# 00_EEG_AFE.net
KiCad netlist of a schematic drawn in Altium Designer
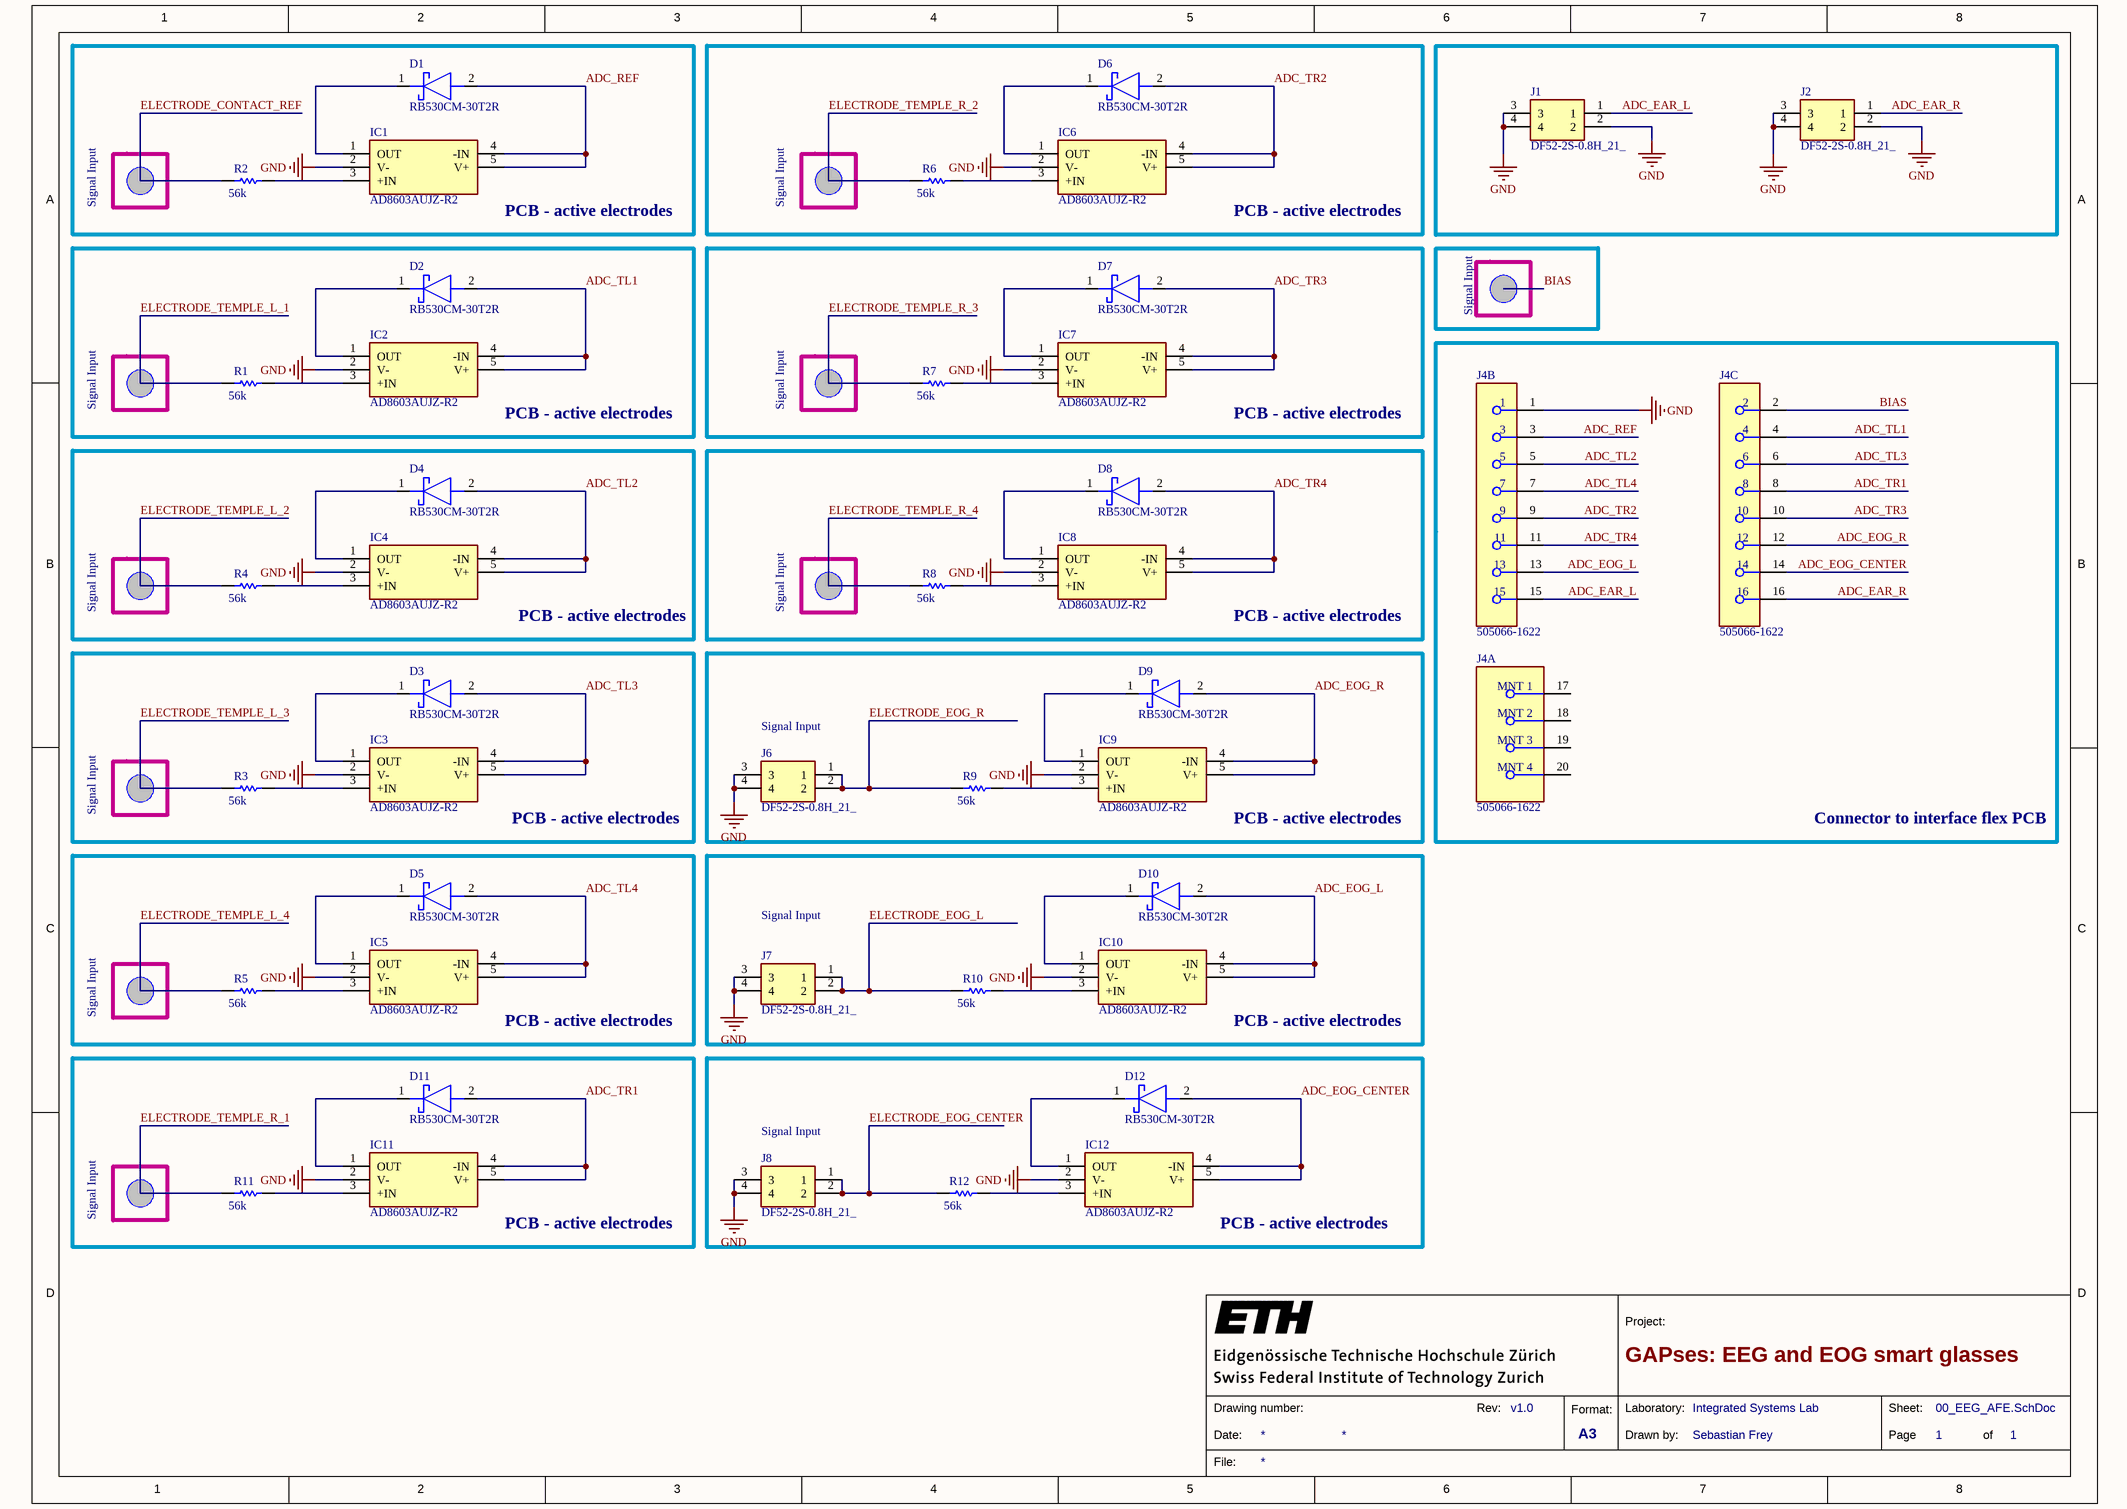
[diagram p0: 00_EEG_AFE.SchDoc]

(export (version "E")
  (design (tool "Eeschema 10.0.6"))
  (components
    (comp (ref "D1")
      (value "RB530CM-30T2R")
      (footprint "SamacSys:RB886CST2RA")
      (description "Schottky Diode")
      (fields (field (name "MOUSER PART NUMBER") "755-RB530CM-30T2R"))
      (libsource (lib "*") (part "RB530CM-30T2R"))
    )
    (comp (ref "D2")
      (value "RB530CM-30T2R")
      (footprint "SamacSys:RB886CST2RA")
      (description "Schottky Diode")
      (fields (field (name "MOUSER PART NUMBER") "755-RB530CM-30T2R"))
      (libsource (lib "*") (part "RB530CM-30T2R"))
    )
    (comp (ref "D3")
      (value "RB530CM-30T2R")
      (footprint "SamacSys:RB886CST2RA")
      (description "Schottky Diode")
      (fields (field (name "MOUSER PART NUMBER") "755-RB530CM-30T2R"))
      (libsource (lib "*") (part "RB530CM-30T2R"))
    )
    (comp (ref "D4")
      (value "RB530CM-30T2R")
      (footprint "SamacSys:RB886CST2RA")
      (description "Schottky Diode")
      (fields (field (name "MOUSER PART NUMBER") "755-RB530CM-30T2R"))
      (libsource (lib "*") (part "RB530CM-30T2R"))
    )
    (comp (ref "D5")
      (value "RB530CM-30T2R")
      (footprint "SamacSys:RB886CST2RA")
      (description "Schottky Diode")
      (fields (field (name "MOUSER PART NUMBER") "755-RB530CM-30T2R"))
      (libsource (lib "*") (part "RB530CM-30T2R"))
    )
    (comp (ref "D6")
      (value "RB530CM-30T2R")
      (footprint "SamacSys:RB886CST2RA")
      (description "Schottky Diode")
      (fields (field (name "MOUSER PART NUMBER") "755-RB530CM-30T2R"))
      (libsource (lib "*") (part "RB530CM-30T2R"))
    )
    (comp (ref "D7")
      (value "RB530CM-30T2R")
      (footprint "SamacSys:RB886CST2RA")
      (description "Schottky Diode")
      (fields (field (name "MOUSER PART NUMBER") "755-RB530CM-30T2R"))
      (libsource (lib "*") (part "RB530CM-30T2R"))
    )
    (comp (ref "D8")
      (value "RB530CM-30T2R")
      (footprint "SamacSys:RB886CST2RA")
      (description "Schottky Diode")
      (fields (field (name "MOUSER PART NUMBER") "755-RB530CM-30T2R"))
      (libsource (lib "*") (part "RB530CM-30T2R"))
    )
    (comp (ref "D9")
      (value "RB530CM-30T2R")
      (footprint "SamacSys:RB886CST2RA")
      (description "Schottky Diode")
      (fields (field (name "MOUSER PART NUMBER") "755-RB530CM-30T2R"))
      (libsource (lib "*") (part "RB530CM-30T2R"))
    )
    (comp (ref "D10")
      (value "RB530CM-30T2R")
      (footprint "SamacSys:RB886CST2RA")
      (description "Schottky Diode")
      (fields (field (name "MOUSER PART NUMBER") "755-RB530CM-30T2R"))
      (libsource (lib "*") (part "RB530CM-30T2R"))
    )
    (comp (ref "D11")
      (value "RB530CM-30T2R")
      (footprint "SamacSys:RB886CST2RA")
      (description "Schottky Diode")
      (fields (field (name "MOUSER PART NUMBER") "755-RB530CM-30T2R"))
      (libsource (lib "*") (part "RB530CM-30T2R"))
    )
    (comp (ref "D12")
      (value "RB530CM-30T2R")
      (footprint "SamacSys:RB886CST2RA")
      (description "Schottky Diode")
      (fields (field (name "MOUSER PART NUMBER") "755-RB530CM-30T2R"))
      (libsource (lib "*") (part "RB530CM-30T2R"))
    )
    (comp (ref "IC1")
      (value "AD8603AUJZ-R2")
      (footprint "EEG_PcbLib:SOT95P280X100-5N")
      (description "Integrated Circuit")
      (libsource (lib "EEG_SchLib") (part "AD8603AUJZ-R2"))
    )
    (comp (ref "IC2")
      (value "AD8603AUJZ-R2")
      (footprint "EEG_PcbLib:SOT95P280X100-5N")
      (description "Integrated Circuit")
      (libsource (lib "EEG_SchLib") (part "AD8603AUJZ-R2"))
    )
    (comp (ref "IC3")
      (value "AD8603AUJZ-R2")
      (footprint "EEG_PcbLib:SOT95P280X100-5N")
      (description "Integrated Circuit")
      (libsource (lib "EEG_SchLib") (part "AD8603AUJZ-R2"))
    )
    (comp (ref "IC4")
      (value "AD8603AUJZ-R2")
      (footprint "EEG_PcbLib:SOT95P280X100-5N")
      (description "Integrated Circuit")
      (libsource (lib "EEG_SchLib") (part "AD8603AUJZ-R2"))
    )
    (comp (ref "IC5")
      (value "AD8603AUJZ-R2")
      (footprint "EEG_PcbLib:SOT95P280X100-5N")
      (description "Integrated Circuit")
      (libsource (lib "EEG_SchLib") (part "AD8603AUJZ-R2"))
    )
    (comp (ref "IC6")
      (value "AD8603AUJZ-R2")
      (footprint "EEG_PcbLib:SOT95P280X100-5N")
      (description "Integrated Circuit")
      (libsource (lib "EEG_SchLib") (part "AD8603AUJZ-R2"))
    )
    (comp (ref "IC7")
      (value "AD8603AUJZ-R2")
      (footprint "EEG_PcbLib:SOT95P280X100-5N")
      (description "Integrated Circuit")
      (libsource (lib "EEG_SchLib") (part "AD8603AUJZ-R2"))
    )
    (comp (ref "IC8")
      (value "AD8603AUJZ-R2")
      (footprint "EEG_PcbLib:SOT95P280X100-5N")
      (description "Integrated Circuit")
      (libsource (lib "EEG_SchLib") (part "AD8603AUJZ-R2"))
    )
    (comp (ref "IC9")
      (value "AD8603AUJZ-R2")
      (footprint "EEG_PcbLib:SOT95P280X100-5N")
      (description "Integrated Circuit")
      (libsource (lib "EEG_SchLib") (part "AD8603AUJZ-R2"))
    )
    (comp (ref "IC10")
      (value "AD8603AUJZ-R2")
      (footprint "EEG_PcbLib:SOT95P280X100-5N")
      (description "Integrated Circuit")
      (libsource (lib "EEG_SchLib") (part "AD8603AUJZ-R2"))
    )
    (comp (ref "IC11")
      (value "AD8603AUJZ-R2")
      (footprint "EEG_PcbLib:SOT95P280X100-5N")
      (description "Integrated Circuit")
      (libsource (lib "EEG_SchLib") (part "AD8603AUJZ-R2"))
    )
    (comp (ref "IC12")
      (value "AD8603AUJZ-R2")
      (footprint "EEG_PcbLib:SOT95P280X100-5N")
      (description "Integrated Circuit")
      (libsource (lib "EEG_SchLib") (part "AD8603AUJZ-R2"))
    )
    (comp (ref "J1")
      (value "DF52-2S-0.8H_21_")
      (footprint "SamacSys:DF522S08H21")
      (description "Connector")
      (fields
        (field (name "MANUFACTURER_PART_NUMBER") "DF52-2S-0.8H(21)")
        (field (name "MOUSER PART NUMBER") "798-DF52-2S-0.8H21")
      )
      (libsource (lib "SamacSys") (part "DF52-2S-0.8H_21_"))
    )
    (comp (ref "J2")
      (value "DF52-2S-0.8H_21_")
      (footprint "SamacSys:DF522S08H21")
      (description "Connector")
      (fields
        (field (name "MANUFACTURER_PART_NUMBER") "DF52-2S-0.8H(21)")
        (field (name "MOUSER PART NUMBER") "798-DF52-2S-0.8H21")
      )
      (libsource (lib "SamacSys") (part "DF52-2S-0.8H_21_"))
    )
    (comp (ref "J4")
      (value "505066-1622")
      (footprint "FP-505066-1622-MFG")
      (description "CONN RCPT 16POS SMD GOLD")
      (libsource (lib "Altium Content Vault") (part "9cd4949b7c36534f8c09468ececd60b"))
    )
    (comp (ref "J6")
      (value "DF52-2S-0.8H_21_")
      (footprint "SamacSys:DF522S08H21")
      (description "Connector")
      (fields
        (field (name "MANUFACTURER_PART_NUMBER") "DF52-2S-0.8H(21)")
        (field (name "MOUSER PART NUMBER") "798-DF52-2S-0.8H21")
      )
      (libsource (lib "SamacSys") (part "DF52-2S-0.8H_21_"))
    )
    (comp (ref "J7")
      (value "DF52-2S-0.8H_21_")
      (footprint "SamacSys:DF522S08H21")
      (description "Connector")
      (fields
        (field (name "MANUFACTURER_PART_NUMBER") "DF52-2S-0.8H(21)")
        (field (name "MOUSER PART NUMBER") "798-DF52-2S-0.8H21")
      )
      (libsource (lib "SamacSys") (part "DF52-2S-0.8H_21_"))
    )
    (comp (ref "J8")
      (value "DF52-2S-0.8H_21_")
      (footprint "SamacSys:DF522S08H21")
      (description "Connector")
      (fields
        (field (name "MANUFACTURER_PART_NUMBER") "DF52-2S-0.8H(21)")
        (field (name "MOUSER PART NUMBER") "798-DF52-2S-0.8H21")
      )
      (libsource (lib "SamacSys") (part "DF52-2S-0.8H_21_"))
    )
    (comp (ref "R1")
      (value "RC0402JR-0756KL")
      (footprint "RESC1005X40X25LL05T10")
      (fields (field (name "MANUFACTURER") "Yageo / Phycomp") (field (name "RESISTANCE") "56k"))
      (libsource (lib "Altium Content Vault") (part "RES"))
    )
    (comp (ref "R2")
      (value "RC0402JR-0756KL")
      (footprint "RESC1005X40X25LL05T10")
      (fields (field (name "MANUFACTURER") "Yageo / Phycomp") (field (name "RESISTANCE") "56k"))
      (libsource (lib "Altium Content Vault") (part "RES"))
    )
    (comp (ref "R3")
      (value "RC0402JR-0756KL")
      (footprint "RESC1005X40X25LL05T10")
      (fields (field (name "MANUFACTURER") "Yageo / Phycomp") (field (name "RESISTANCE") "56k"))
      (libsource (lib "Altium Content Vault") (part "RES"))
    )
    (comp (ref "R4")
      (value "RC0402JR-0756KL")
      (footprint "RESC1005X40X25LL05T10")
      (fields (field (name "MANUFACTURER") "Yageo / Phycomp") (field (name "RESISTANCE") "56k"))
      (libsource (lib "Altium Content Vault") (part "RES"))
    )
    (comp (ref "R5")
      (value "RC0402JR-0756KL")
      (footprint "RESC1005X40X25LL05T10")
      (fields (field (name "MANUFACTURER") "Yageo / Phycomp") (field (name "RESISTANCE") "56k"))
      (libsource (lib "Altium Content Vault") (part "RES"))
    )
    (comp (ref "R6")
      (value "RC0402JR-0756KL")
      (footprint "RESC1005X40X25LL05T10")
      (fields (field (name "MANUFACTURER") "Yageo / Phycomp") (field (name "RESISTANCE") "56k"))
      (libsource (lib "Altium Content Vault") (part "RES"))
    )
    (comp (ref "R7")
      (value "RC0402JR-0756KL")
      (footprint "RESC1005X40X25LL05T10")
      (fields (field (name "MANUFACTURER") "Yageo / Phycomp") (field (name "RESISTANCE") "56k"))
      (libsource (lib "Altium Content Vault") (part "RES"))
    )
    (comp (ref "R8")
      (value "RC0402JR-0756KL")
      (footprint "RESC1005X40X25LL05T10")
      (fields (field (name "MANUFACTURER") "Yageo / Phycomp") (field (name "RESISTANCE") "56k"))
      (libsource (lib "Altium Content Vault") (part "RES"))
    )
    (comp (ref "R9")
      (value "RC0402JR-0756KL")
      (footprint "RESC1005X40X25LL05T10")
      (fields (field (name "MANUFACTURER") "Yageo / Phycomp") (field (name "RESISTANCE") "56k"))
      (libsource (lib "Altium Content Vault") (part "RES"))
    )
    (comp (ref "R10")
      (value "RC0402JR-0756KL")
      (footprint "RESC1005X40X25LL05T10")
      (fields (field (name "MANUFACTURER") "Yageo / Phycomp") (field (name "RESISTANCE") "56k"))
      (libsource (lib "Altium Content Vault") (part "RES"))
    )
    (comp (ref "R11")
      (value "RC0402JR-0756KL")
      (footprint "RESC1005X40X25LL05T10")
      (fields (field (name "MANUFACTURER") "Yageo / Phycomp") (field (name "RESISTANCE") "56k"))
      (libsource (lib "Altium Content Vault") (part "RES"))
    )
    (comp (ref "R12")
      (value "RC0402JR-0756KL")
      (footprint "RESC1005X40X25LL05T10")
      (fields (field (name "MANUFACTURER") "Yageo / Phycomp") (field (name "RESISTANCE") "56k"))
      (libsource (lib "Altium Content Vault") (part "RES"))
    )
  )
  (nets
    (net (code "1") (name "/ADC_EAR_L") (class "Default")
      (node (ref "J1") (pin "1") (pinfunction "1_1") (pintype "passive"))
      (node (ref "J4") (pin "15") (pinfunction "15_15") (pintype "passive"))
    )
    (net (code "2") (name "/ADC_EAR_R") (class "Default")
      (node (ref "J2") (pin "1") (pinfunction "1_1") (pintype "passive"))
      (node (ref "J4") (pin "16") (pinfunction "16_16") (pintype "passive"))
    )
    (net (code "3") (name "/ADC_EOG_CENTER") (class "Default")
      (node (ref "D12") (pin "2") (pinfunction "A_2") (pintype "passive"))
      (node (ref "IC12") (pin "4") (pinfunction "-IN_4") (pintype "passive"))
      (node (ref "IC12") (pin "5") (pinfunction "V+_5") (pintype "passive"))
      (node (ref "J4") (pin "14") (pinfunction "14_14") (pintype "passive"))
    )
    (net (code "4") (name "/ADC_EOG_L") (class "Default")
      (node (ref "D10") (pin "2") (pinfunction "A_2") (pintype "passive"))
      (node (ref "IC10") (pin "4") (pinfunction "-IN_4") (pintype "passive"))
      (node (ref "IC10") (pin "5") (pinfunction "V+_5") (pintype "passive"))
      (node (ref "J4") (pin "13") (pinfunction "13_13") (pintype "passive"))
    )
    (net (code "5") (name "/ADC_EOG_R") (class "Default")
      (node (ref "D9") (pin "2") (pinfunction "A_2") (pintype "passive"))
      (node (ref "IC9") (pin "4") (pinfunction "-IN_4") (pintype "passive"))
      (node (ref "IC9") (pin "5") (pinfunction "V+_5") (pintype "passive"))
      (node (ref "J4") (pin "12") (pinfunction "12_12") (pintype "passive"))
    )
    (net (code "6") (name "/ADC_REF") (class "Default")
      (node (ref "D1") (pin "2") (pinfunction "A_2") (pintype "passive"))
      (node (ref "IC1") (pin "4") (pinfunction "-IN_4") (pintype "passive"))
      (node (ref "IC1") (pin "5") (pinfunction "V+_5") (pintype "passive"))
      (node (ref "J4") (pin "3") (pinfunction "3_3") (pintype "passive"))
    )
    (net (code "7") (name "/ADC_TL1") (class "Default")
      (node (ref "D2") (pin "2") (pinfunction "A_2") (pintype "passive"))
      (node (ref "IC2") (pin "4") (pinfunction "-IN_4") (pintype "passive"))
      (node (ref "IC2") (pin "5") (pinfunction "V+_5") (pintype "passive"))
      (node (ref "J4") (pin "4") (pinfunction "4_4") (pintype "passive"))
    )
    (net (code "8") (name "/ADC_TL2") (class "Default")
      (node (ref "D4") (pin "2") (pinfunction "A_2") (pintype "passive"))
      (node (ref "IC4") (pin "4") (pinfunction "-IN_4") (pintype "passive"))
      (node (ref "IC4") (pin "5") (pinfunction "V+_5") (pintype "passive"))
      (node (ref "J4") (pin "5") (pinfunction "5_5") (pintype "passive"))
    )
    (net (code "9") (name "/ADC_TL3") (class "Default")
      (node (ref "D3") (pin "2") (pinfunction "A_2") (pintype "passive"))
      (node (ref "IC3") (pin "4") (pinfunction "-IN_4") (pintype "passive"))
      (node (ref "IC3") (pin "5") (pinfunction "V+_5") (pintype "passive"))
      (node (ref "J4") (pin "6") (pinfunction "6_6") (pintype "passive"))
    )
    (net (code "10") (name "/ADC_TL4") (class "Default")
      (node (ref "D5") (pin "2") (pinfunction "A_2") (pintype "passive"))
      (node (ref "IC5") (pin "4") (pinfunction "-IN_4") (pintype "passive"))
      (node (ref "IC5") (pin "5") (pinfunction "V+_5") (pintype "passive"))
      (node (ref "J4") (pin "7") (pinfunction "7_7") (pintype "passive"))
    )
    (net (code "11") (name "/ADC_TR1") (class "Default")
      (node (ref "D11") (pin "2") (pinfunction "A_2") (pintype "passive"))
      (node (ref "IC11") (pin "4") (pinfunction "-IN_4") (pintype "passive"))
      (node (ref "IC11") (pin "5") (pinfunction "V+_5") (pintype "passive"))
      (node (ref "J4") (pin "8") (pinfunction "8_8") (pintype "passive"))
    )
    (net (code "12") (name "/ADC_TR2") (class "Default")
      (node (ref "D6") (pin "2") (pinfunction "A_2") (pintype "passive"))
      (node (ref "IC6") (pin "4") (pinfunction "-IN_4") (pintype "passive"))
      (node (ref "IC6") (pin "5") (pinfunction "V+_5") (pintype "passive"))
      (node (ref "J4") (pin "9") (pinfunction "9_9") (pintype "passive"))
    )
    (net (code "13") (name "/ADC_TR3") (class "Default")
      (node (ref "D7") (pin "2") (pinfunction "A_2") (pintype "passive"))
      (node (ref "IC7") (pin "4") (pinfunction "-IN_4") (pintype "passive"))
      (node (ref "IC7") (pin "5") (pinfunction "V+_5") (pintype "passive"))
      (node (ref "J4") (pin "10") (pinfunction "10_10") (pintype "passive"))
    )
    (net (code "14") (name "/ADC_TR4") (class "Default")
      (node (ref "D8") (pin "2") (pinfunction "A_2") (pintype "passive"))
      (node (ref "IC8") (pin "4") (pinfunction "-IN_4") (pintype "passive"))
      (node (ref "IC8") (pin "5") (pinfunction "V+_5") (pintype "passive"))
      (node (ref "J4") (pin "11") (pinfunction "11_11") (pintype "passive"))
    )
    (net (code "15") (name "/BIAS") (class "Default")
      (node (ref "J4") (pin "2") (pinfunction "2_2") (pintype "passive"))
    )
    (net (code "16") (name "/ELECTRODE_CONTACT_REF") (class "Default")
      (node (ref "R2") (pin "1") (pinfunction "1_1") (pintype "passive"))
    )
    (net (code "17") (name "/ELECTRODE_EOG_CENTER") (class "Default")
      (node (ref "J8") (pin "1") (pinfunction "1_1") (pintype "passive"))
      (node (ref "J8") (pin "2") (pinfunction "2_2") (pintype "passive"))
      (node (ref "R12") (pin "1") (pinfunction "1_1") (pintype "passive"))
    )
    (net (code "18") (name "/ELECTRODE_EOG_L") (class "Default")
      (node (ref "J7") (pin "1") (pinfunction "1_1") (pintype "passive"))
      (node (ref "J7") (pin "2") (pinfunction "2_2") (pintype "passive"))
      (node (ref "R10") (pin "1") (pinfunction "1_1") (pintype "passive"))
    )
    (net (code "19") (name "/ELECTRODE_EOG_R") (class "Default")
      (node (ref "J6") (pin "1") (pinfunction "1_1") (pintype "passive"))
      (node (ref "J6") (pin "2") (pinfunction "2_2") (pintype "passive"))
      (node (ref "R9") (pin "1") (pinfunction "1_1") (pintype "passive"))
    )
    (net (code "20") (name "/ELECTRODE_TEMPLE_L_1") (class "Default")
      (node (ref "R1") (pin "1") (pinfunction "1_1") (pintype "passive"))
    )
    (net (code "21") (name "/ELECTRODE_TEMPLE_L_2") (class "Default")
      (node (ref "R4") (pin "1") (pinfunction "1_1") (pintype "passive"))
    )
    (net (code "22") (name "/ELECTRODE_TEMPLE_L_3") (class "Default")
      (node (ref "R3") (pin "1") (pinfunction "1_1") (pintype "passive"))
    )
    (net (code "23") (name "/ELECTRODE_TEMPLE_L_4") (class "Default")
      (node (ref "R5") (pin "1") (pinfunction "1_1") (pintype "passive"))
    )
    (net (code "24") (name "/ELECTRODE_TEMPLE_R_1") (class "Default")
      (node (ref "R11") (pin "1") (pinfunction "1_1") (pintype "passive"))
    )
    (net (code "25") (name "/ELECTRODE_TEMPLE_R_2") (class "Default")
      (node (ref "R6") (pin "1") (pinfunction "1_1") (pintype "passive"))
    )
    (net (code "26") (name "/ELECTRODE_TEMPLE_R_3") (class "Default")
      (node (ref "R7") (pin "1") (pinfunction "1_1") (pintype "passive"))
    )
    (net (code "27") (name "/ELECTRODE_TEMPLE_R_4") (class "Default")
      (node (ref "R8") (pin "1") (pinfunction "1_1") (pintype "passive"))
    )
    (net (code "28") (name "GND") (class "Default")
      (node (ref "IC1") (pin "2") (pinfunction "V-_2") (pintype "passive"))
      (node (ref "IC10") (pin "2") (pinfunction "V-_2") (pintype "passive"))
      (node (ref "IC11") (pin "2") (pinfunction "V-_2") (pintype "passive"))
      (node (ref "IC12") (pin "2") (pinfunction "V-_2") (pintype "passive"))
      (node (ref "IC2") (pin "2") (pinfunction "V-_2") (pintype "passive"))
      (node (ref "IC3") (pin "2") (pinfunction "V-_2") (pintype "passive"))
      (node (ref "IC4") (pin "2") (pinfunction "V-_2") (pintype "passive"))
      (node (ref "IC5") (pin "2") (pinfunction "V-_2") (pintype "passive"))
      (node (ref "IC6") (pin "2") (pinfunction "V-_2") (pintype "passive"))
      (node (ref "IC7") (pin "2") (pinfunction "V-_2") (pintype "passive"))
      (node (ref "IC8") (pin "2") (pinfunction "V-_2") (pintype "passive"))
      (node (ref "IC9") (pin "2") (pinfunction "V-_2") (pintype "passive"))
      (node (ref "J1") (pin "2") (pinfunction "2_2") (pintype "passive"))
      (node (ref "J1") (pin "3") (pinfunction "3_3") (pintype "passive"))
      (node (ref "J1") (pin "4") (pinfunction "4_4") (pintype "passive"))
      (node (ref "J2") (pin "2") (pinfunction "2_2") (pintype "passive"))
      (node (ref "J2") (pin "3") (pinfunction "3_3") (pintype "passive"))
      (node (ref "J2") (pin "4") (pinfunction "4_4") (pintype "passive"))
      (node (ref "J4") (pin "1") (pinfunction "1_1") (pintype "passive"))
      (node (ref "J6") (pin "3") (pinfunction "3_3") (pintype "passive"))
      (node (ref "J6") (pin "4") (pinfunction "4_4") (pintype "passive"))
      (node (ref "J7") (pin "3") (pinfunction "3_3") (pintype "passive"))
      (node (ref "J7") (pin "4") (pinfunction "4_4") (pintype "passive"))
      (node (ref "J8") (pin "3") (pinfunction "3_3") (pintype "passive"))
      (node (ref "J8") (pin "4") (pinfunction "4_4") (pintype "passive"))
    )
    (net (code "29") (name "Net-(D1-K)") (class "Default")
      (node (ref "D1") (pin "1") (pinfunction "K_1") (pintype "passive"))
      (node (ref "IC1") (pin "1") (pinfunction "OUT_1") (pintype "passive"))
    )
    (net (code "30") (name "Net-(D2-K)") (class "Default")
      (node (ref "D2") (pin "1") (pinfunction "K_1") (pintype "passive"))
      (node (ref "IC2") (pin "1") (pinfunction "OUT_1") (pintype "passive"))
    )
    (net (code "31") (name "Net-(D3-K)") (class "Default")
      (node (ref "D3") (pin "1") (pinfunction "K_1") (pintype "passive"))
      (node (ref "IC3") (pin "1") (pinfunction "OUT_1") (pintype "passive"))
    )
    (net (code "32") (name "Net-(D4-K)") (class "Default")
      (node (ref "D4") (pin "1") (pinfunction "K_1") (pintype "passive"))
      (node (ref "IC4") (pin "1") (pinfunction "OUT_1") (pintype "passive"))
    )
    (net (code "33") (name "Net-(D5-K)") (class "Default")
      (node (ref "D5") (pin "1") (pinfunction "K_1") (pintype "passive"))
      (node (ref "IC5") (pin "1") (pinfunction "OUT_1") (pintype "passive"))
    )
    (net (code "34") (name "Net-(D6-K)") (class "Default")
      (node (ref "D6") (pin "1") (pinfunction "K_1") (pintype "passive"))
      (node (ref "IC6") (pin "1") (pinfunction "OUT_1") (pintype "passive"))
    )
    (net (code "35") (name "Net-(D7-K)") (class "Default")
      (node (ref "D7") (pin "1") (pinfunction "K_1") (pintype "passive"))
      (node (ref "IC7") (pin "1") (pinfunction "OUT_1") (pintype "passive"))
    )
    (net (code "36") (name "Net-(D8-K)") (class "Default")
      (node (ref "D8") (pin "1") (pinfunction "K_1") (pintype "passive"))
      (node (ref "IC8") (pin "1") (pinfunction "OUT_1") (pintype "passive"))
    )
    (net (code "37") (name "Net-(D9-K)") (class "Default")
      (node (ref "D9") (pin "1") (pinfunction "K_1") (pintype "passive"))
      (node (ref "IC9") (pin "1") (pinfunction "OUT_1") (pintype "passive"))
    )
    (net (code "38") (name "Net-(D10-K)") (class "Default")
      (node (ref "D10") (pin "1") (pinfunction "K_1") (pintype "passive"))
      (node (ref "IC10") (pin "1") (pinfunction "OUT_1") (pintype "passive"))
    )
    (net (code "39") (name "Net-(D11-K)") (class "Default")
      (node (ref "D11") (pin "1") (pinfunction "K_1") (pintype "passive"))
      (node (ref "IC11") (pin "1") (pinfunction "OUT_1") (pintype "passive"))
    )
    (net (code "40") (name "Net-(D12-K)") (class "Default")
      (node (ref "D12") (pin "1") (pinfunction "K_1") (pintype "passive"))
      (node (ref "IC12") (pin "1") (pinfunction "OUT_1") (pintype "passive"))
    )
    (net (code "41") (name "Net-(IC1-+IN)") (class "Default")
      (node (ref "IC1") (pin "3") (pinfunction "+IN_3") (pintype "passive"))
      (node (ref "R2") (pin "2") (pinfunction "2_2") (pintype "passive"))
    )
    (net (code "42") (name "Net-(IC2-+IN)") (class "Default")
      (node (ref "IC2") (pin "3") (pinfunction "+IN_3") (pintype "passive"))
      (node (ref "R1") (pin "2") (pinfunction "2_2") (pintype "passive"))
    )
    (net (code "43") (name "Net-(IC3-+IN)") (class "Default")
      (node (ref "IC3") (pin "3") (pinfunction "+IN_3") (pintype "passive"))
      (node (ref "R3") (pin "2") (pinfunction "2_2") (pintype "passive"))
    )
    (net (code "44") (name "Net-(IC4-+IN)") (class "Default")
      (node (ref "IC4") (pin "3") (pinfunction "+IN_3") (pintype "passive"))
      (node (ref "R4") (pin "2") (pinfunction "2_2") (pintype "passive"))
    )
    (net (code "45") (name "Net-(IC5-+IN)") (class "Default")
      (node (ref "IC5") (pin "3") (pinfunction "+IN_3") (pintype "passive"))
      (node (ref "R5") (pin "2") (pinfunction "2_2") (pintype "passive"))
    )
    (net (code "46") (name "Net-(IC6-+IN)") (class "Default")
      (node (ref "IC6") (pin "3") (pinfunction "+IN_3") (pintype "passive"))
      (node (ref "R6") (pin "2") (pinfunction "2_2") (pintype "passive"))
    )
    (net (code "47") (name "Net-(IC7-+IN)") (class "Default")
      (node (ref "IC7") (pin "3") (pinfunction "+IN_3") (pintype "passive"))
      (node (ref "R7") (pin "2") (pinfunction "2_2") (pintype "passive"))
    )
    (net (code "48") (name "Net-(IC8-+IN)") (class "Default")
      (node (ref "IC8") (pin "3") (pinfunction "+IN_3") (pintype "passive"))
      (node (ref "R8") (pin "2") (pinfunction "2_2") (pintype "passive"))
    )
    (net (code "49") (name "Net-(IC9-+IN)") (class "Default")
      (node (ref "IC9") (pin "3") (pinfunction "+IN_3") (pintype "passive"))
      (node (ref "R9") (pin "2") (pinfunction "2_2") (pintype "passive"))
    )
    (net (code "50") (name "Net-(IC10-+IN)") (class "Default")
      (node (ref "IC10") (pin "3") (pinfunction "+IN_3") (pintype "passive"))
      (node (ref "R10") (pin "2") (pinfunction "2_2") (pintype "passive"))
    )
    (net (code "51") (name "Net-(IC11-+IN)") (class "Default")
      (node (ref "IC11") (pin "3") (pinfunction "+IN_3") (pintype "passive"))
      (node (ref "R11") (pin "2") (pinfunction "2_2") (pintype "passive"))
    )
    (net (code "52") (name "Net-(IC12-+IN)") (class "Default")
      (node (ref "IC12") (pin "3") (pinfunction "+IN_3") (pintype "passive"))
      (node (ref "R12") (pin "2") (pinfunction "2_2") (pintype "passive"))
    )
    (net (code "53") (name "unconnected-(J4A-MNT_1-Pad17)") (class "Default")
      (node (ref "J4") (pin "17") (pinfunction "MNT_1_17") (pintype "passive"))
    )
    (net (code "54") (name "unconnected-(J4A-MNT_2-Pad18)") (class "Default")
      (node (ref "J4") (pin "18") (pinfunction "MNT_2_18") (pintype "passive"))
    )
    (net (code "55") (name "unconnected-(J4A-MNT_3-Pad19)") (class "Default")
      (node (ref "J4") (pin "19") (pinfunction "MNT_3_19") (pintype "passive"))
    )
    (net (code "56") (name "unconnected-(J4A-MNT_4-Pad20)") (class "Default")
      (node (ref "J4") (pin "20") (pinfunction "MNT_4_20") (pintype "passive"))
    )
  )
)
